# board_4_pg2.net
KiCad netlist of a schematic drawn in Altium Designer
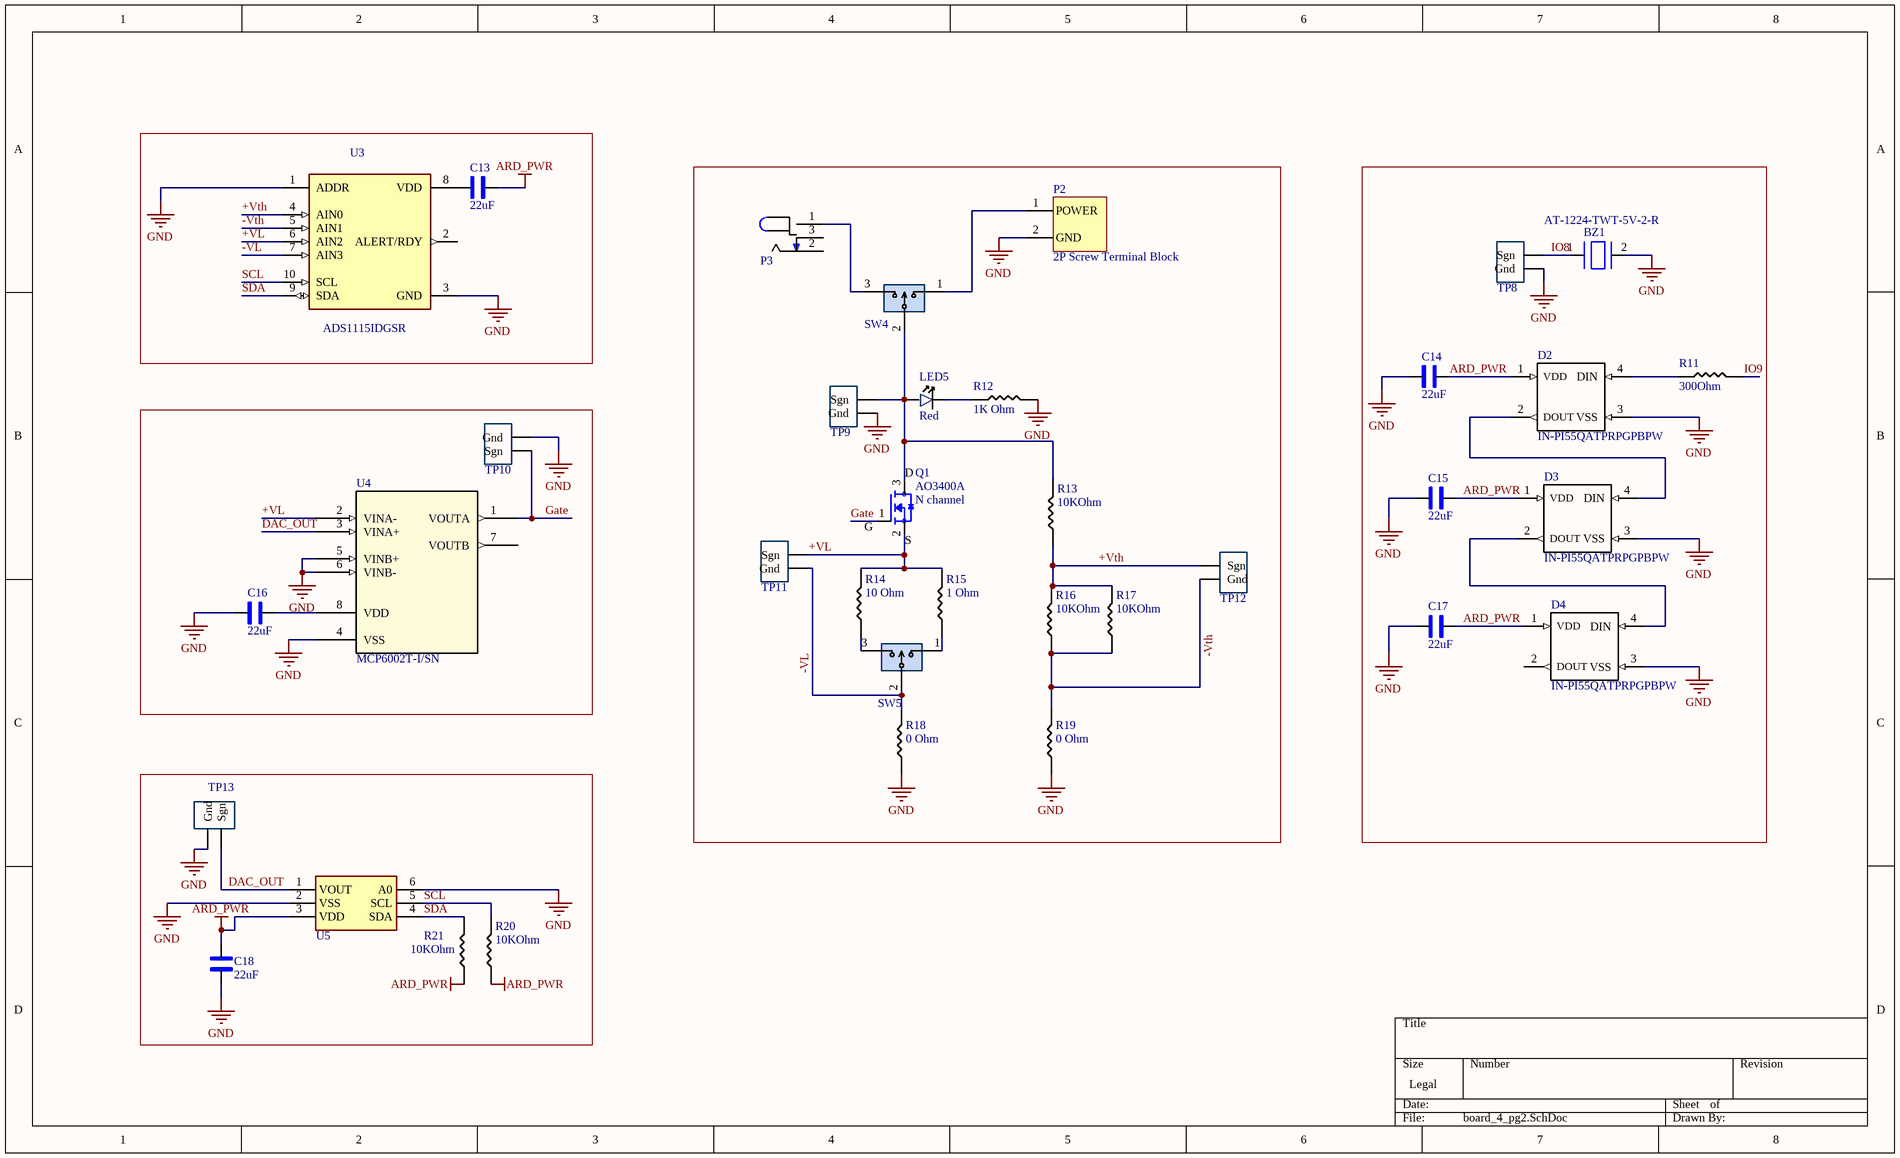
[diagram p0: board_4_pg2.SchDoc]

(export (version "E")
  (design (tool "Eeschema 10.0.6"))
  (components
    (comp (ref "BZ1")
      (value "AT-1224-TWT-5V-2-R")
      (footprint "BUZZER- TH")
      (fields (field (name "MFR PART #") "AT-1224-TWT-5V-2-R"))
      (libsource (lib "ECEN5730Lib_2023_05_DS") (part "BUZZER_1"))
    )
    (comp (ref "C13")
      (value "22uF")
      (footprint "1206_Passive_Capacitor")
      (description "22uF ±10% 25V X5R 1206 Multilayer Ceramic Capacitors MLCC - SMD/SMT RoHS")
      (fields (field (name "MFR PART #") "CL31A226KAHNNNE") (field (name "LCSC PART#") "C12891"))
      (libsource (lib "ECEN5730Lib_2023_05_DS") (part "C_22uF_1206"))
    )
    (comp (ref "C14")
      (value "22uF")
      (footprint "1206_Passive_Capacitor")
      (description "22uF ±10% 25V X5R 1206 Multilayer Ceramic Capacitors MLCC - SMD/SMT RoHS")
      (fields (field (name "MFR PART #") "CL31A226KAHNNNE") (field (name "LCSC PART#") "C12891"))
      (libsource (lib "ECEN5730Lib_2023_05_DS") (part "C_22uF_1206"))
    )
    (comp (ref "C15")
      (value "22uF")
      (footprint "1206_Passive_Capacitor")
      (description "22uF ±10% 25V X5R 1206 Multilayer Ceramic Capacitors MLCC - SMD/SMT RoHS")
      (fields (field (name "MFR PART #") "CL31A226KAHNNNE") (field (name "LCSC PART#") "C12891"))
      (libsource (lib "ECEN5730Lib_2023_05_DS") (part "C_22uF_1206"))
    )
    (comp (ref "C16")
      (value "22uF")
      (footprint "1206_Passive_Capacitor")
      (description "22uF ±10% 25V X5R 1206 Multilayer Ceramic Capacitors MLCC - SMD/SMT RoHS")
      (fields (field (name "MFR PART #") "CL31A226KAHNNNE") (field (name "LCSC PART#") "C12891"))
      (libsource (lib "ECEN5730Lib_2023_05_DS") (part "C_22uF_1206"))
    )
    (comp (ref "C17")
      (value "22uF")
      (footprint "1206_Passive_Capacitor")
      (description "22uF ±10% 25V X5R 1206 Multilayer Ceramic Capacitors MLCC - SMD/SMT RoHS")
      (fields (field (name "MFR PART #") "CL31A226KAHNNNE") (field (name "LCSC PART#") "C12891"))
      (libsource (lib "ECEN5730Lib_2023_05_DS") (part "C_22uF_1206"))
    )
    (comp (ref "C18")
      (value "22uF")
      (footprint "1206_Passive_Capacitor")
      (description "22uF ±10% 25V X5R 1206 Multilayer Ceramic Capacitors MLCC - SMD/SMT RoHS")
      (fields (field (name "MFR PART #") "CL31A226KAHNNNE") (field (name "LCSC PART#") "C12891"))
      (libsource (lib "ECEN5730Lib_2023_05_DS") (part "C_22uF_1206"))
    )
    (comp (ref "D2")
      (value "IN-PI55QATPRPGPBPW")
      (footprint "SERIAL_LED - duplicate")
      (fields
        (field (name "LCSC PART#") "C2843785")
        (field (name "MFR PART #") "XL-5050RGBC-WS2812B")
        (field (name "MANUFACTURER") "XINGLIGHT")
      )
      (libsource (lib "ECEN5730Lib_2023_05_DS") (part "LED_Smart"))
    )
    (comp (ref "D3")
      (value "IN-PI55QATPRPGPBPW")
      (footprint "SERIAL_LED - duplicate")
      (fields
        (field (name "LCSC PART#") "C2843785")
        (field (name "MFR PART #") "XL-5050RGBC-WS2812B")
        (field (name "MANUFACTURER") "XINGLIGHT")
      )
      (libsource (lib "ECEN5730Lib_2023_05_DS") (part "LED_Smart"))
    )
    (comp (ref "D4")
      (value "IN-PI55QATPRPGPBPW")
      (footprint "SERIAL_LED - duplicate")
      (fields
        (field (name "LCSC PART#") "C2843785")
        (field (name "MFR PART #") "XL-5050RGBC-WS2812B")
        (field (name "MANUFACTURER") "XINGLIGHT")
      )
      (libsource (lib "ECEN5730Lib_2023_05_DS") (part "LED_Smart"))
    )
    (comp (ref "LED5")
      (value "Red")
      (footprint "LED_1206")
      (description "Red 621~631nm 1206 Light Emitting Diodes (LED) RoHS")
      (fields (field (name "MFR PART #") "15-21/R6C-FQ1R1B/2T") (field (name "LCSC PART#") "C93133"))
      (libsource (lib "ECEN5730Lib_2023_05_DS") (part "LED_RED_1206"))
    )
    (comp (ref "P2")
      (value "2P Screw Terminal Block")
      (footprint "P_Terminal block 3.5mm-pitch")
      (description "Green Straight pin 3.5mm  pitch; P=3.5mm  Screw terminal ROHS")
      (fields (field (name "MFR PART #") "KF350-3.5-2P") (field (name "MANUFACTURER") "Cixi Kefa Elec"))
      (libsource (lib "ECEN5730Lib_2023_05_DS") (part "P_Terminal block"))
    )
    (comp (ref "P3")
      (value "Power Jack")
      (footprint "Power_Jack")
      (description "Power Barrel Connector Jack 2.10mm ID (0.083\"), 5.50mm OD (0.217\") Through Hole, Right Angle")
      (fields (field (name "MFR PART #") "PJ-102A") (field (name "LCSC PART#") "C136744"))
      (libsource (lib "ECEN5730Lib_2023_05_DS") (part "P_Power Jack"))
    )
    (comp (ref "Q1")
      (value "AO3400A")
      (footprint "N-MOSFET")
      (description "MOSFET N Trench 30V 5.7A 1.5V @ 250uA 26.5 m? @ 5.7A,10V SOT-23-3L RoHS")
      (fields (field (name "LCSC PART#") "C20917") (field (name "ALTIUM_VALUE") "N channel"))
      (libsource (lib "ECEN5730Lib_2023_05_DS") (part "Q_Nch_MOSFET"))
    )
    (comp (ref "R11")
      (value "300Ohm")
      (footprint "1206_Passive_Resitor")
      (description "CHIP RESISTOR - SURFACE MOUNT 300OHMS ±1% 1/4W 1206 ROHS")
      (fields (field (name "MFR PART #") "1206W4F3000T5E") (field (name "LCSC PART#") "C17887"))
      (libsource (lib "ECEN5730Lib_2023_05_DS") (part "R_300Ohm_1206"))
    )
    (comp (ref "R12")
      (value "1K Ohm")
      (footprint "1206_Passive_Resitor")
      (description "CHIP RESISTOR - SURFACE MOUNT 1KOHMS ±1% 1/4W 1206 ROHS")
      (fields (field (name "MFR PART #") "RNCP1206FTD1K00CT") (field (name "LCSC PART#") "C4410"))
      (libsource (lib "ECEN5730Lib_2023_05_DS") (part "R_1K_1206"))
    )
    (comp (ref "R13")
      (value "10KOhm")
      (footprint "1206_Passive_Resitor")
      (description "10 kOhms ±5% 0.25W, 1/4W Chip Resistor 1206 (3216 Metric) Automotive AEC-Q200 Thick Film")
      (fields (field (name "MFR PART #") "RMCF1206FT10K0") (field (name "LCSC PART#") "C17902"))
      (libsource (lib "ECEN5730Lib_2023_05_DS") (part "R_10KOhm_1206"))
    )
    (comp (ref "R14")
      (value "10 Ohm")
      (footprint "1206_Passive_Resitor")
      (description "CHIP RESISTOR - SURFACE MOUNT 0.1OHMS ±1% 1/4W 1206 ROHS")
      (fields (field (name "MFR PART #") "1206W4F100JT5E") (field (name "LCSC PART#") "C17903"))
      (libsource (lib "ECEN5730Lib_2023_05_DS") (part "R_10Ohm_1206"))
    )
    (comp (ref "R15")
      (value "1 Ohm")
      (footprint "1206_Passive_Resitor")
      (description "CHIP RESISTOR - SURFACE MOUNT 0.1OHMS ±1% 1/4W 1206 ROHS")
      (fields (field (name "MFR PART #") "1206W4F100JT5E") (field (name "LCSC PART#") "C17903"))
      (libsource (lib "ECEN5730Lib_2023_05_DS") (part "R_10Ohm_1206"))
    )
    (comp (ref "R16")
      (value "10KOhm")
      (footprint "1206_Passive_Resitor")
      (description "10 kOhms ±5% 0.25W, 1/4W Chip Resistor 1206 (3216 Metric) Automotive AEC-Q200 Thick Film")
      (fields (field (name "MFR PART #") "RMCF1206FT10K0") (field (name "LCSC PART#") "C17902"))
      (libsource (lib "ECEN5730Lib_2023_05_DS") (part "R_10KOhm_1206"))
    )
    (comp (ref "R17")
      (value "10KOhm")
      (footprint "1206_Passive_Resitor")
      (description "10 kOhms ±5% 0.25W, 1/4W Chip Resistor 1206 (3216 Metric) Automotive AEC-Q200 Thick Film")
      (fields (field (name "MFR PART #") "RMCF1206FT10K0") (field (name "LCSC PART#") "C17902"))
      (libsource (lib "ECEN5730Lib_2023_05_DS") (part "R_10KOhm_1206"))
    )
    (comp (ref "R18")
      (value "0 Ohm")
      (footprint "1206_Passive_Resitor")
      (description "CHIP RESISTOR - SURFACE MOUNT 0OHMS ±1% 1/4W 1206 ROHS")
      (fields (field (name "MFR PART #") "1206W4F0000T5E") (field (name "LCSC PART#") "C17888"))
      (libsource (lib "ECEN5730Lib_2023_05_DS") (part "R_0Ohm_1206"))
    )
    (comp (ref "R19")
      (value "0 Ohm")
      (footprint "1206_Passive_Resitor")
      (description "CHIP RESISTOR - SURFACE MOUNT 0OHMS ±1% 1/4W 1206 ROHS")
      (fields (field (name "MFR PART #") "1206W4F0000T5E") (field (name "LCSC PART#") "C17888"))
      (libsource (lib "ECEN5730Lib_2023_05_DS") (part "R_0Ohm_1206"))
    )
    (comp (ref "R20")
      (value "10KOhm")
      (footprint "1206_Passive_Resitor")
      (description "10 kOhms ±5% 0.25W, 1/4W Chip Resistor 1206 (3216 Metric) Automotive AEC-Q200 Thick Film")
      (fields (field (name "MFR PART #") "RMCF1206FT10K0") (field (name "LCSC PART#") "C17902"))
      (libsource (lib "ECEN5730Lib_2023_05_DS") (part "R_10KOhm_1206"))
    )
    (comp (ref "R21")
      (value "10KOhm")
      (footprint "1206_Passive_Resitor")
      (description "10 kOhms ±5% 0.25W, 1/4W Chip Resistor 1206 (3216 Metric) Automotive AEC-Q200 Thick Film")
      (fields (field (name "MFR PART #") "RMCF1206FT10K0") (field (name "LCSC PART#") "C17902"))
      (libsource (lib "ECEN5730Lib_2023_05_DS") (part "R_10KOhm_1206"))
    )
    (comp (ref "SW4")
      (value "PREC003SAAN-RC")
      (footprint "3_PIN_100mil")
      (description "Connector Header Through Hole 3 position 0.100\" (2.54mm)")
      (fields (field (name "LCSC PART#") "C49257"))
      (libsource (lib "ECEN5730Lib_2023_05_DS") (part "SW_3Pin_100mil_Switch"))
    )
    (comp (ref "SW5")
      (value "PREC003SAAN-RC")
      (footprint "3_PIN_100mil")
      (description "Connector Header Through Hole 3 position 0.100\" (2.54mm)")
      (fields (field (name "LCSC PART#") "C49257"))
      (libsource (lib "ECEN5730Lib_2023_05_DS") (part "SW_3Pin_100mil_Switch"))
    )
    (comp (ref "TP8")
      (value "10x Probe TP")
      (footprint "TP10x_Probe")
      (description "Test Point 300 mil centers")
      (libsource (lib "ECEN5730Lib_2023_05_DS") (part "TP_10x_Probe"))
    )
    (comp (ref "TP9")
      (value "10x Probe TP")
      (footprint "TP10x_Probe")
      (description "Test Point 300 mil centers")
      (libsource (lib "ECEN5730Lib_2023_05_DS") (part "TP_10x_Probe"))
    )
    (comp (ref "TP10")
      (value "10x Probe TP")
      (footprint "TP10x_Probe")
      (description "Test Point 300 mil centers")
      (libsource (lib "") (part "TP_10x_Probe_2"))
    )
    (comp (ref "TP11")
      (value "10x Probe TP")
      (footprint "TP10x_Probe")
      (description "Test Point 300 mil centers")
      (libsource (lib "ECEN5730Lib_2023_05_DS") (part "TP_10x_Probe"))
    )
    (comp (ref "TP12")
      (value "10x Probe TP")
      (footprint "TP10x_Probe")
      (description "Test Point 300 mil centers")
      (libsource (lib "") (part "TP_10x_Probe_1"))
    )
    (comp (ref "TP13")
      (value "10x Probe TP")
      (footprint "TP10x_Probe")
      (description "Test Point 300 mil centers")
      (libsource (lib "") (part "TP_10x_Probe_1"))
    )
    (comp (ref "U3")
      (value "ADS1115IDGSR")
      (footprint "ADC_ADS1115IDGSR")
      (description "16-Bit ADC with Integrated MUX, PGA, Comparator, Oscillator, and Reference 10-VSSOP -40 to 125")
      (fields (field (name "LCSC PART#") "C37593"))
      (libsource (lib "ECEN5730Lib_2023_05_DS") (part "U_ADC_ADS1115IDGSR"))
    )
    (comp (ref "U4")
      (value "MCP6002T-I/SN")
      (footprint "SOIC127P600X175-8N")
      (description "0.6 V/us 2 1MHz 1.8V ~ 6V 100μA General Purpose SOIC-8_150mil  Operational Amplifier ROHS")
      (fields (field (name "MFR") "Microchip") (field (name "LCSC PART#") "C7377"))
      (libsource (lib "ECEN5730Lib_2023_05_DS") (part "U_MCP6002T-I/SN"))
    )
    (comp (ref "U5")
      (value "DAC IC")
      (footprint "MCP4725")
      (description "IC DAC 12BIT V-OUT SOT23-6")
      (fields (field (name "LCSC PART#") "C144198") (field (name "MFR PART #") "MCP4725A0T-E/CH"))
      (libsource (lib "ECEN5730Lib_2023_05_DS") (part "U_MCP4725A0T-E/CH"))
    )
  )
  (nets
    (net (code "1") (name "/+VL") (class "Default")
      (node (ref "Q1") (pin "2") (pinfunction "S_2") (pintype "passive"))
      (node (ref "R14") (pin "2") (pinfunction "2_2") (pintype "passive"))
      (node (ref "R15") (pin "2") (pinfunction "2_2") (pintype "passive"))
      (node (ref "TP11") (pin "1") (pinfunction "Sgn_1") (pintype "passive"))
      (node (ref "U3") (pin "6") (pinfunction "AIN2_6") (pintype "input"))
      (node (ref "U4") (pin "2") (pinfunction "VINA-_2") (pintype "input"))
    )
    (net (code "2") (name "/+Vth") (class "Default")
      (node (ref "R13") (pin "1") (pinfunction "1_1") (pintype "passive"))
      (node (ref "R16") (pin "2") (pinfunction "2_2") (pintype "passive"))
      (node (ref "R17") (pin "2") (pinfunction "2_2") (pintype "passive"))
      (node (ref "TP12") (pin "1") (pinfunction "Sgn_1") (pintype "passive"))
      (node (ref "U3") (pin "4") (pinfunction "AIN0_4") (pintype "input"))
    )
    (net (code "3") (name "/-VL") (class "Default")
      (node (ref "R18") (pin "2") (pinfunction "2_2") (pintype "passive"))
      (node (ref "SW5") (pin "2") (pinfunction "2_2") (pintype "passive"))
      (node (ref "TP11") (pin "2") (pinfunction "Gnd_2") (pintype "passive"))
      (node (ref "U3") (pin "7") (pinfunction "AIN3_7") (pintype "input"))
    )
    (net (code "4") (name "/-Vth") (class "Default")
      (node (ref "R16") (pin "1") (pinfunction "1_1") (pintype "passive"))
      (node (ref "R17") (pin "1") (pinfunction "1_1") (pintype "passive"))
      (node (ref "R19") (pin "2") (pinfunction "2_2") (pintype "passive"))
      (node (ref "TP12") (pin "2") (pinfunction "Gnd_2") (pintype "passive"))
      (node (ref "U3") (pin "5") (pinfunction "AIN1_5") (pintype "input"))
    )
    (net (code "5") (name "/DAC_OUT") (class "Default")
      (node (ref "TP13") (pin "1") (pinfunction "Sgn_1") (pintype "passive"))
      (node (ref "U4") (pin "3") (pinfunction "VINA+_3") (pintype "input"))
      (node (ref "U5") (pin "1") (pinfunction "VOUT_1") (pintype "passive"))
    )
    (net (code "6") (name "/Gate") (class "Default")
      (node (ref "Q1") (pin "1") (pinfunction "G_1") (pintype "passive"))
      (node (ref "TP10") (pin "1") (pinfunction "Sgn_1") (pintype "passive"))
      (node (ref "U4") (pin "1") (pinfunction "VOUTA_1") (pintype "output"))
    )
    (net (code "7") (name "/IO8") (class "Default")
      (node (ref "BZ1") (pin "1") (pinfunction "BZ1_1") (pintype "passive"))
      (node (ref "TP8") (pin "1") (pinfunction "Sgn_1") (pintype "passive"))
    )
    (net (code "8") (name "/IO9") (class "Default")
      (node (ref "R11") (pin "2") (pinfunction "2_2") (pintype "passive"))
    )
    (net (code "9") (name "/SCL") (class "Default")
      (node (ref "R20") (pin "2") (pinfunction "2_2") (pintype "passive"))
      (node (ref "U3") (pin "10") (pinfunction "SCL_10") (pintype "input"))
      (node (ref "U5") (pin "5") (pinfunction "SCL_5") (pintype "passive"))
    )
    (net (code "10") (name "/SDA") (class "Default")
      (node (ref "R21") (pin "2") (pinfunction "2_2") (pintype "passive"))
      (node (ref "U3") (pin "9") (pinfunction "SDA_9") (pintype "bidirectional"))
      (node (ref "U5") (pin "4") (pinfunction "SDA_4") (pintype "passive"))
    )
    (net (code "11") (name "ARD_PWR") (class "Default")
      (node (ref "C13") (pin "1") (pinfunction "1_1") (pintype "passive"))
      (node (ref "C14") (pin "1") (pinfunction "1_1") (pintype "passive"))
      (node (ref "C15") (pin "1") (pinfunction "1_1") (pintype "passive"))
      (node (ref "C17") (pin "1") (pinfunction "1_1") (pintype "passive"))
      (node (ref "C18") (pin "2") (pinfunction "2_2") (pintype "passive"))
      (node (ref "D2") (pin "1") (pinfunction "VDD_1") (pintype "input"))
      (node (ref "D3") (pin "1") (pinfunction "VDD_1") (pintype "input"))
      (node (ref "D4") (pin "1") (pinfunction "VDD_1") (pintype "input"))
      (node (ref "R20") (pin "1") (pinfunction "1_1") (pintype "passive"))
      (node (ref "R21") (pin "1") (pinfunction "1_1") (pintype "passive"))
      (node (ref "U5") (pin "3") (pinfunction "VDD_3") (pintype "passive"))
    )
    (net (code "12") (name "GND") (class "Default")
      (node (ref "BZ1") (pin "2") (pinfunction "BZ2_2") (pintype "passive"))
      (node (ref "C14") (pin "2") (pinfunction "2_2") (pintype "passive"))
      (node (ref "C15") (pin "2") (pinfunction "2_2") (pintype "passive"))
      (node (ref "C16") (pin "2") (pinfunction "2_2") (pintype "passive"))
      (node (ref "C17") (pin "2") (pinfunction "2_2") (pintype "passive"))
      (node (ref "C18") (pin "1") (pinfunction "1_1") (pintype "passive"))
      (node (ref "D2") (pin "3") (pinfunction "VSS_3") (pintype "input"))
      (node (ref "D3") (pin "3") (pinfunction "VSS_3") (pintype "input"))
      (node (ref "D4") (pin "3") (pinfunction "VSS_3") (pintype "input"))
      (node (ref "P2") (pin "2") (pinfunction "GND_2") (pintype "passive"))
      (node (ref "R12") (pin "2") (pinfunction "2_2") (pintype "passive"))
      (node (ref "R18") (pin "1") (pinfunction "1_1") (pintype "passive"))
      (node (ref "R19") (pin "1") (pinfunction "1_1") (pintype "passive"))
      (node (ref "TP10") (pin "2") (pinfunction "Gnd_2") (pintype "passive"))
      (node (ref "TP13") (pin "2") (pinfunction "Gnd_2") (pintype "passive"))
      (node (ref "TP8") (pin "2") (pinfunction "Gnd_2") (pintype "passive"))
      (node (ref "TP9") (pin "2") (pinfunction "Gnd_2") (pintype "passive"))
      (node (ref "U3") (pin "1") (pinfunction "ADDR_1") (pintype "passive"))
      (node (ref "U3") (pin "3") (pinfunction "GND_3") (pintype "power_in"))
      (node (ref "U4") (pin "4") (pinfunction "VSS_4") (pintype "passive"))
      (node (ref "U4") (pin "5") (pinfunction "VINB+_5") (pintype "input"))
      (node (ref "U4") (pin "6") (pinfunction "VINB-_6") (pintype "input"))
      (node (ref "U5") (pin "2") (pinfunction "VSS_2") (pintype "passive"))
      (node (ref "U5") (pin "6") (pinfunction "A0_6") (pintype "passive"))
    )
    (net (code "13") (name "Net-(D2-DIN)") (class "Default")
      (node (ref "D2") (pin "4") (pinfunction "DIN_4") (pintype "input"))
      (node (ref "R11") (pin "1") (pinfunction "1_1") (pintype "passive"))
    )
    (net (code "14") (name "Net-(D2-DOUT)") (class "Default")
      (node (ref "D2") (pin "2") (pinfunction "DOUT_2") (pintype "output"))
      (node (ref "D3") (pin "4") (pinfunction "DIN_4") (pintype "input"))
    )
    (net (code "15") (name "Net-(D3-DOUT)") (class "Default")
      (node (ref "D3") (pin "2") (pinfunction "DOUT_2") (pintype "output"))
      (node (ref "D4") (pin "4") (pinfunction "DIN_4") (pintype "input"))
    )
    (net (code "16") (name "Net-(LED5-Pad2)") (class "Default")
      (node (ref "LED5") (pin "2") (pinfunction "2_2") (pintype "passive"))
      (node (ref "R12") (pin "1") (pinfunction "1_1") (pintype "passive"))
    )
    (net (code "17") (name "Net-(P2-POWER)") (class "Default")
      (node (ref "P2") (pin "1") (pinfunction "POWER_1") (pintype "passive"))
      (node (ref "SW4") (pin "1") (pinfunction "1_1") (pintype "passive"))
    )
    (net (code "18") (name "Net-(P3-Pad1)") (class "Default")
      (node (ref "P3") (pin "1") (pinfunction "1_1") (pintype "power_in"))
      (node (ref "SW4") (pin "3") (pinfunction "3_3") (pintype "passive"))
    )
    (net (code "19") (name "Net-(Q1-D)") (class "Default")
      (node (ref "LED5") (pin "1") (pinfunction "1_1") (pintype "passive"))
      (node (ref "Q1") (pin "3") (pinfunction "D_3") (pintype "passive"))
      (node (ref "R13") (pin "2") (pinfunction "2_2") (pintype "passive"))
      (node (ref "SW4") (pin "2") (pinfunction "2_2") (pintype "passive"))
      (node (ref "TP9") (pin "1") (pinfunction "Sgn_1") (pintype "passive"))
    )
    (net (code "20") (name "Net-(R14-Pad1)") (class "Default")
      (node (ref "R14") (pin "1") (pinfunction "1_1") (pintype "passive"))
      (node (ref "SW5") (pin "3") (pinfunction "3_3") (pintype "passive"))
    )
    (net (code "21") (name "Net-(R15-Pad1)") (class "Default")
      (node (ref "R15") (pin "1") (pinfunction "1_1") (pintype "passive"))
      (node (ref "SW5") (pin "1") (pinfunction "1_1") (pintype "passive"))
    )
    (net (code "22") (name "Net-(U3-VDD)") (class "Default")
      (node (ref "C13") (pin "2") (pinfunction "2_2") (pintype "passive"))
      (node (ref "U3") (pin "8") (pinfunction "VDD_8") (pintype "power_in"))
    )
    (net (code "23") (name "Net-(U4-VDD)") (class "Default")
      (node (ref "C16") (pin "1") (pinfunction "1_1") (pintype "passive"))
      (node (ref "U4") (pin "8") (pinfunction "VDD_8") (pintype "passive"))
    )
    (net (code "24") (name "unconnected-(D4-DOUT-Pad2)") (class "Default")
      (node (ref "D4") (pin "2") (pinfunction "DOUT_2") (pintype "output"))
    )
    (net (code "25") (name "unconnected-(P3-Pad2)") (class "Default")
      (node (ref "P3") (pin "2") (pinfunction "2_2") (pintype "power_in"))
    )
    (net (code "26") (name "unconnected-(P3-Pad3)") (class "Default")
      (node (ref "P3") (pin "3") (pinfunction "3_3") (pintype "power_in"))
    )
    (net (code "27") (name "unconnected-(U3-ALERT{slash}RDY-Pad2)") (class "Default")
      (node (ref "U3") (pin "2") (pinfunction "ALERT/RDY_2") (pintype "output"))
    )
    (net (code "28") (name "unconnected-(U4-VOUTB-Pad7)") (class "Default")
      (node (ref "U4") (pin "7") (pinfunction "VOUTB_7") (pintype "output"))
    )
  )
)
